# Pushbuttons.net
KiCad netlist of a schematic drawn in Altium Designer
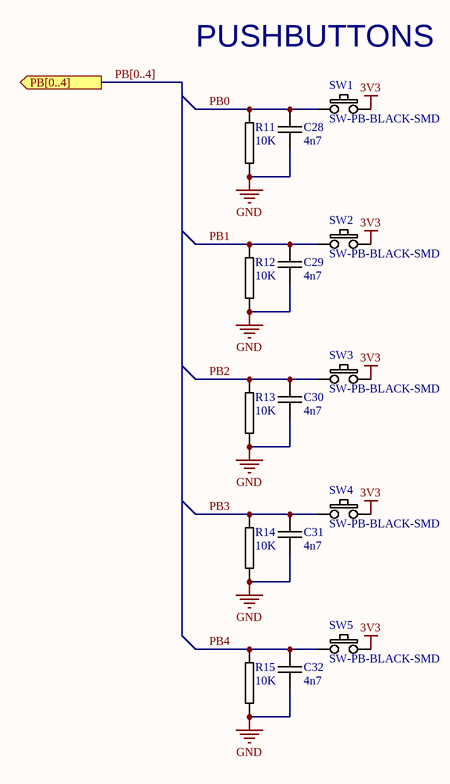
[diagram p0: Pushbuttons.SchDoc]

(export (version "E")
  (design (tool "Eeschema 10.0.6"))
  (components
    (comp (ref "C28")
      (value "4n7")
      (footprint "0603C-TBD")
      (description "CAPACITOR 0603 CERAMIC")
      (libsource (lib "RVA_Altium_Library") (part "0603C-4N7"))
    )
    (comp (ref "C29")
      (value "4n7")
      (footprint "0603C-TBD")
      (description "CAPACITOR 0603 CERAMIC")
      (libsource (lib "RVA_Altium_Library") (part "0603C-4N7"))
    )
    (comp (ref "C30")
      (value "4n7")
      (footprint "0603C-TBD")
      (description "CAPACITOR 0603 CERAMIC")
      (libsource (lib "RVA_Altium_Library") (part "0603C-4N7"))
    )
    (comp (ref "C31")
      (value "4n7")
      (footprint "0603C-TBD")
      (description "CAPACITOR 0603 CERAMIC")
      (libsource (lib "RVA_Altium_Library") (part "0603C-4N7"))
    )
    (comp (ref "C32")
      (value "4n7")
      (footprint "0603C-TBD")
      (description "CAPACITOR 0603 CERAMIC")
      (libsource (lib "RVA_Altium_Library") (part "0603C-4N7"))
    )
    (comp (ref "R11")
      (value "10K")
      (footprint "0603R-10K")
      (description "GENERIC RESISTOR 0603")
      (fields (field (name "MANUFACTURER") "Stackpole Electronics Inc") (field (name "TOLERANCE") "±1%"))
      (libsource (lib "RVA_Altium_Library") (part "0603R-10K"))
    )
    (comp (ref "R12")
      (value "10K")
      (footprint "0603R-10K")
      (description "GENERIC RESISTOR 0603")
      (fields (field (name "MANUFACTURER") "Stackpole Electronics Inc") (field (name "TOLERANCE") "±1%"))
      (libsource (lib "RVA_Altium_Library") (part "0603R-10K"))
    )
    (comp (ref "R13")
      (value "10K")
      (footprint "0603R-10K")
      (description "GENERIC RESISTOR 0603")
      (fields (field (name "MANUFACTURER") "Stackpole Electronics Inc") (field (name "TOLERANCE") "±1%"))
      (libsource (lib "RVA_Altium_Library") (part "0603R-10K"))
    )
    (comp (ref "R14")
      (value "10K")
      (footprint "0603R-10K")
      (description "GENERIC RESISTOR 0603")
      (fields (field (name "MANUFACTURER") "Stackpole Electronics Inc") (field (name "TOLERANCE") "±1%"))
      (libsource (lib "RVA_Altium_Library") (part "0603R-10K"))
    )
    (comp (ref "R15")
      (value "10K")
      (footprint "0603R-10K")
      (description "GENERIC RESISTOR 0603")
      (fields (field (name "MANUFACTURER") "Stackpole Electronics Inc") (field (name "TOLERANCE") "±1%"))
      (libsource (lib "RVA_Altium_Library") (part "0603R-10K"))
    )
    (comp (ref "SW1")
      (value "SW-PB-BLACK-SMD")
      (footprint "SW-PB-SMD")
      (description "PUSHBUTTON SWITCH 6MM SMD")
      (libsource (lib "RVA_Altium_Library") (part "SW-PB-BLACK-SMD"))
    )
    (comp (ref "SW2")
      (value "SW-PB-BLACK-SMD")
      (footprint "SW-PB-SMD")
      (description "PUSHBUTTON SWITCH 6MM SMD")
      (libsource (lib "RVA_Altium_Library") (part "SW-PB-BLACK-SMD"))
    )
    (comp (ref "SW3")
      (value "SW-PB-BLACK-SMD")
      (footprint "SW-PB-SMD")
      (description "PUSHBUTTON SWITCH 6MM SMD")
      (libsource (lib "RVA_Altium_Library") (part "SW-PB-BLACK-SMD"))
    )
    (comp (ref "SW4")
      (value "SW-PB-BLACK-SMD")
      (footprint "SW-PB-SMD")
      (description "PUSHBUTTON SWITCH 6MM SMD")
      (libsource (lib "RVA_Altium_Library") (part "SW-PB-BLACK-SMD"))
    )
    (comp (ref "SW5")
      (value "SW-PB-BLACK-SMD")
      (footprint "SW-PB-SMD")
      (description "PUSHBUTTON SWITCH 6MM SMD")
      (libsource (lib "RVA_Altium_Library") (part "SW-PB-BLACK-SMD"))
    )
  )
  (nets
    (net (code "1") (name "/PB0") (class "Default")
      (node (ref "C28") (pin "1") (pintype "passive"))
      (node (ref "R11") (pin "1") (pintype "passive"))
      (node (ref "SW1") (pin "1") (pintype "passive"))
    )
    (net (code "2") (name "/PB1") (class "Default")
      (node (ref "C29") (pin "1") (pintype "passive"))
      (node (ref "R12") (pin "1") (pintype "passive"))
      (node (ref "SW2") (pin "1") (pintype "passive"))
    )
    (net (code "3") (name "/PB2") (class "Default")
      (node (ref "C30") (pin "1") (pintype "passive"))
      (node (ref "R13") (pin "1") (pintype "passive"))
      (node (ref "SW3") (pin "1") (pintype "passive"))
    )
    (net (code "4") (name "/PB3") (class "Default")
      (node (ref "C31") (pin "1") (pintype "passive"))
      (node (ref "R14") (pin "1") (pintype "passive"))
      (node (ref "SW4") (pin "1") (pintype "passive"))
    )
    (net (code "5") (name "/PB4") (class "Default")
      (node (ref "C32") (pin "1") (pintype "passive"))
      (node (ref "R15") (pin "1") (pintype "passive"))
      (node (ref "SW5") (pin "1") (pintype "passive"))
    )
    (net (code "7") (name "3V3") (class "Default")
      (node (ref "SW1") (pin "2") (pintype "passive"))
      (node (ref "SW2") (pin "2") (pintype "passive"))
      (node (ref "SW3") (pin "2") (pintype "passive"))
      (node (ref "SW4") (pin "2") (pintype "passive"))
      (node (ref "SW5") (pin "2") (pintype "passive"))
    )
    (net (code "8") (name "GND") (class "Default")
      (node (ref "C28") (pin "2") (pintype "passive"))
      (node (ref "C29") (pin "2") (pintype "passive"))
      (node (ref "C30") (pin "2") (pintype "passive"))
      (node (ref "C31") (pin "2") (pintype "passive"))
      (node (ref "C32") (pin "2") (pintype "passive"))
      (node (ref "R11") (pin "2") (pintype "passive"))
      (node (ref "R12") (pin "2") (pintype "passive"))
      (node (ref "R13") (pin "2") (pintype "passive"))
      (node (ref "R14") (pin "2") (pintype "passive"))
      (node (ref "R15") (pin "2") (pintype "passive"))
    )
  )
)
